# Heater.net
KiCad netlist of a schematic drawn in Altium Designer
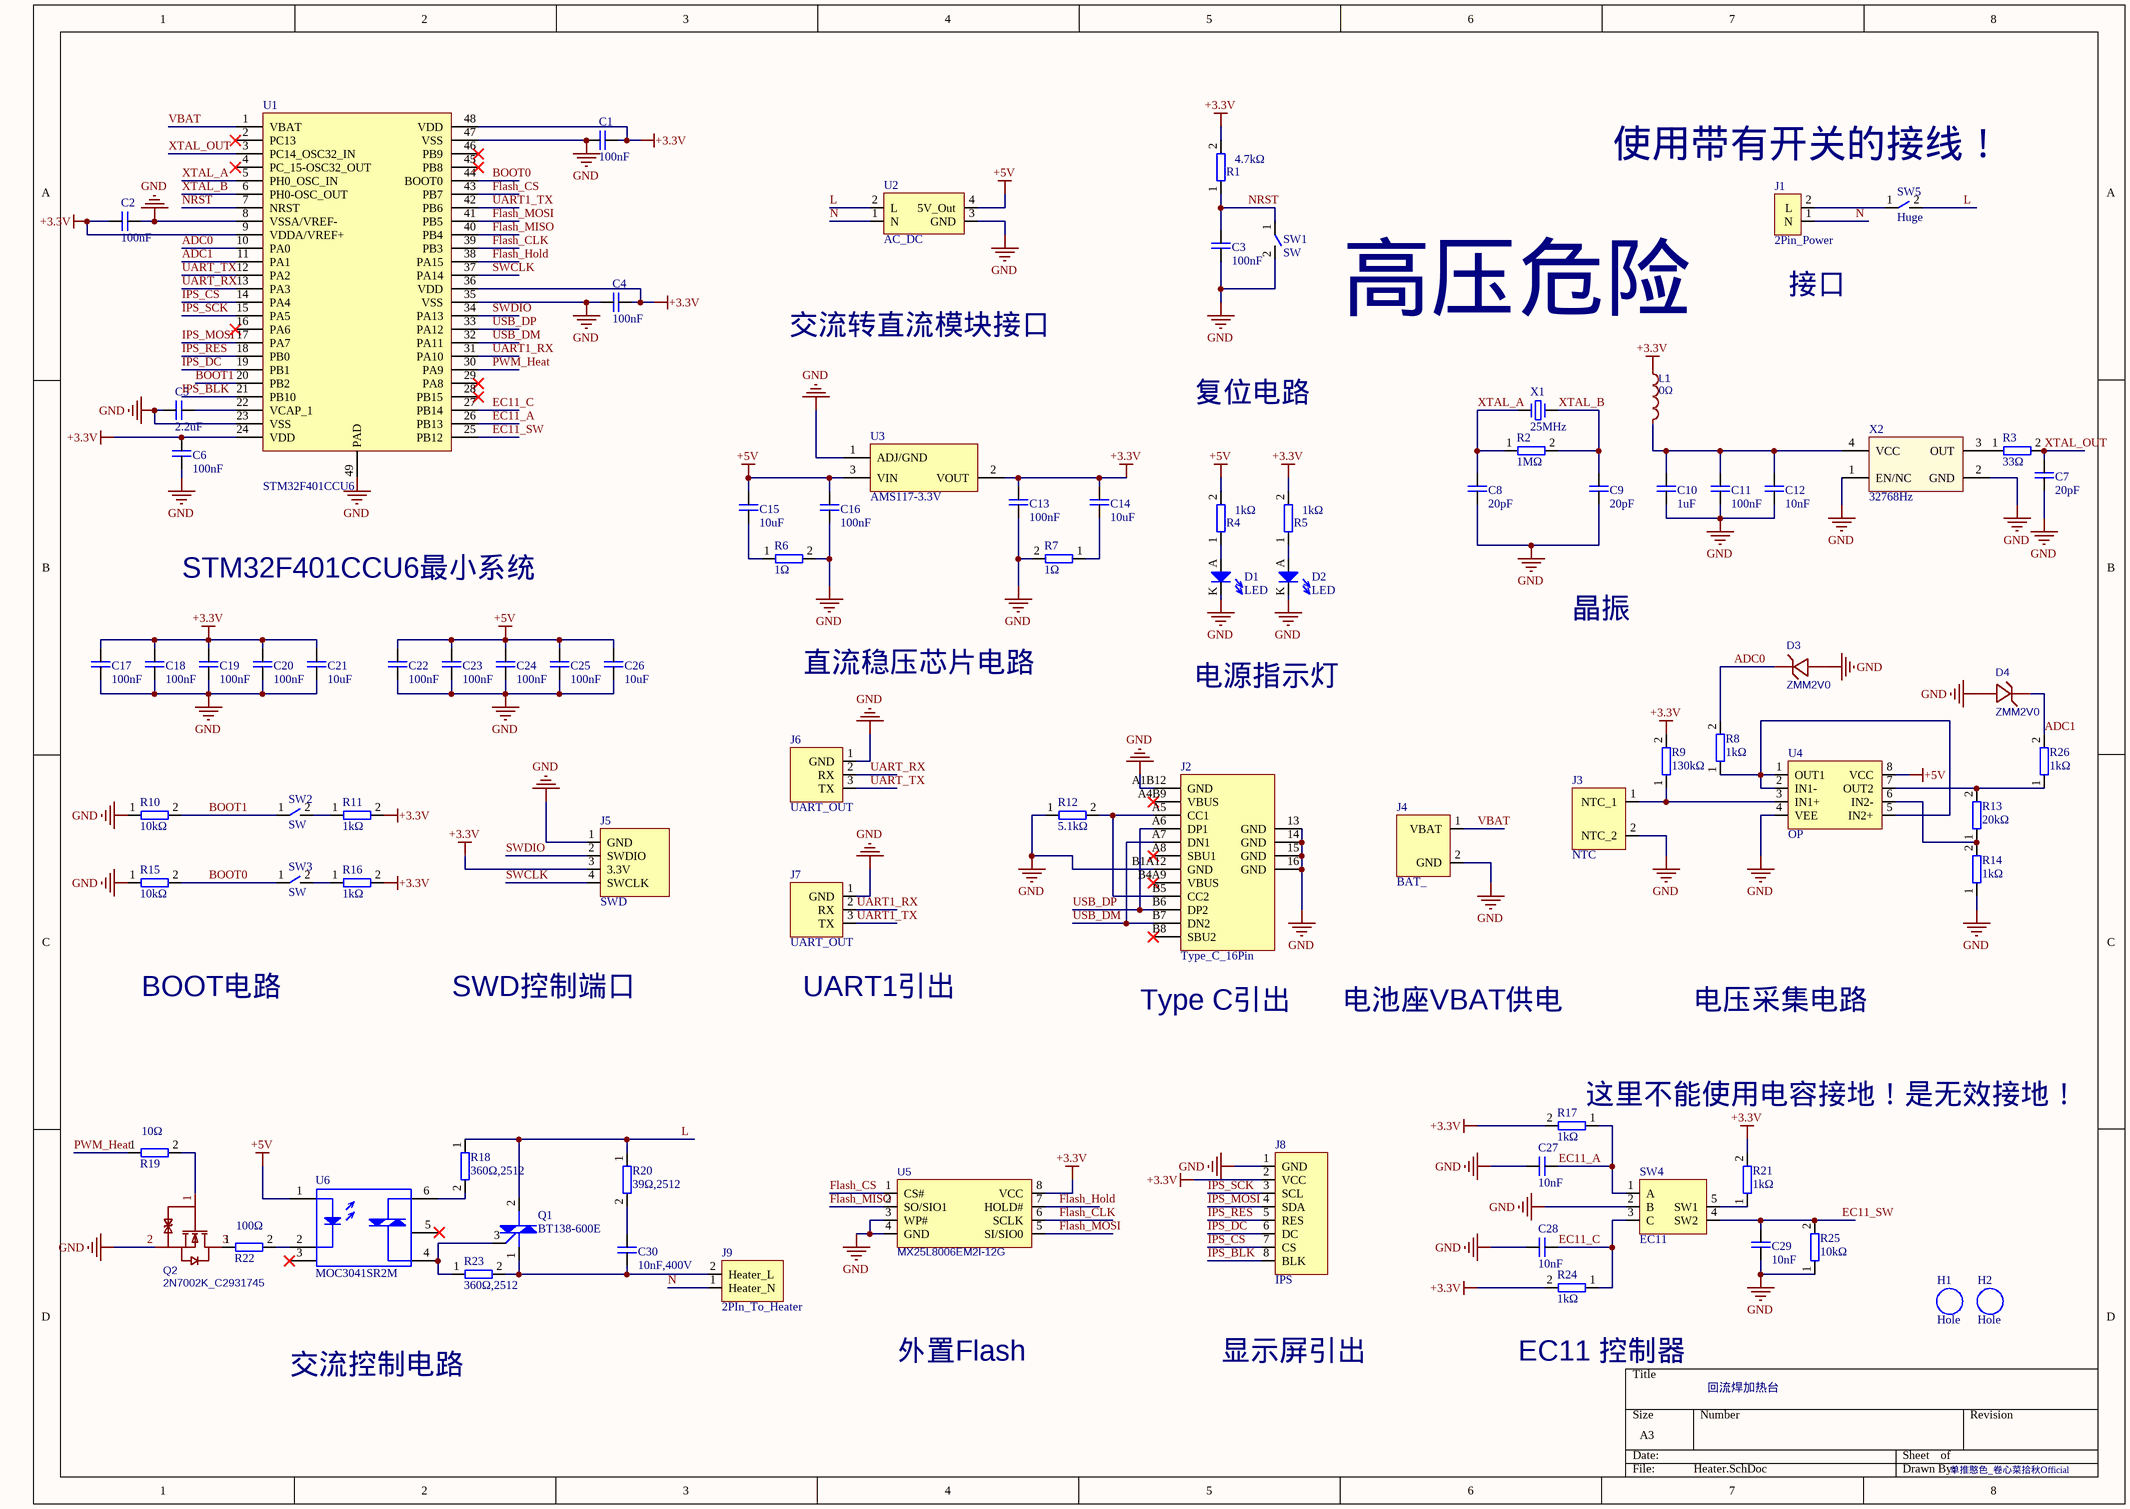
[diagram p0: Heater.SchDoc]

(export (version "E")
  (design (tool "Eeschema 10.0.6"))
  (components
    (comp (ref "C1") (value "100nF") (footprint "0603_C") (libsource (lib "Heater") (part "Capacitor")))
    (comp (ref "C2") (value "100nF") (footprint "0603_C") (libsource (lib "Heater") (part "Capacitor")))
    (comp (ref "C3") (value "100nF") (footprint "0603_C") (libsource (lib "Heater") (part "Capacitor")))
    (comp (ref "C4") (value "100nF") (footprint "0603_C") (libsource (lib "Heater") (part "Capacitor")))
    (comp (ref "C5") (value "2.2uF") (footprint "0603_C") (libsource (lib "Heater") (part "Capacitor")))
    (comp (ref "C6") (value "100nF") (footprint "0603_C") (libsource (lib "Heater") (part "Capacitor")))
    (comp (ref "C7") (value "20pF") (footprint "0603_C") (libsource (lib "Heater") (part "Capacitor")))
    (comp (ref "C8") (value "20pF") (footprint "0603_C") (libsource (lib "Heater") (part "Capacitor")))
    (comp (ref "C9") (value "20pF") (footprint "0603_C") (libsource (lib "Heater") (part "Capacitor")))
    (comp (ref "C10") (value "1uF") (footprint "0603_C") (libsource (lib "Heater") (part "Capacitor")))
    (comp (ref "C11") (value "100nF") (footprint "0603_C") (libsource (lib "Heater") (part "Capacitor")))
    (comp (ref "C12") (value "10nF") (footprint "0603_C") (libsource (lib "Heater") (part "Capacitor")))
    (comp (ref "C13") (value "100nF") (footprint "0603_C") (libsource (lib "Heater") (part "Capacitor")))
    (comp (ref "C14") (value "10uF") (footprint "0603_C") (libsource (lib "Heater") (part "Capacitor")))
    (comp (ref "C15") (value "10uF") (footprint "0603_C") (libsource (lib "Heater") (part "Capacitor")))
    (comp (ref "C16") (value "100nF") (footprint "0603_C") (libsource (lib "Heater") (part "Capacitor")))
    (comp (ref "C17") (value "100nF") (footprint "0603_C") (libsource (lib "Heater") (part "Capacitor")))
    (comp (ref "C18") (value "100nF") (footprint "0603_C") (libsource (lib "Heater") (part "Capacitor")))
    (comp (ref "C19") (value "100nF") (footprint "0603_C") (libsource (lib "Heater") (part "Capacitor")))
    (comp (ref "C20") (value "100nF") (footprint "0603_C") (libsource (lib "Heater") (part "Capacitor")))
    (comp (ref "C21") (value "10uF") (footprint "0603_C") (libsource (lib "Heater") (part "Capacitor")))
    (comp (ref "C22") (value "100nF") (footprint "0603_C") (libsource (lib "Heater") (part "Capacitor")))
    (comp (ref "C23") (value "100nF") (footprint "0603_C") (libsource (lib "Heater") (part "Capacitor")))
    (comp (ref "C24") (value "100nF") (footprint "0603_C") (libsource (lib "Heater") (part "Capacitor")))
    (comp (ref "C25") (value "100nF") (footprint "0603_C") (libsource (lib "Heater") (part "Capacitor")))
    (comp (ref "C26") (value "10uF") (footprint "0603_C") (libsource (lib "Heater") (part "Capacitor")))
    (comp (ref "C27") (value "10nF") (footprint "0603_C") (libsource (lib "Heater") (part "Capacitor")))
    (comp (ref "C28") (value "10nF") (footprint "0603_C") (libsource (lib "Heater") (part "Capacitor")))
    (comp (ref "C29") (value "10nF") (footprint "0603_C") (libsource (lib "Heater") (part "Capacitor")))
    (comp (ref "C30")
      (value "10nF,400V")
      (footprint "2PIN - BigCap")
      (libsource (lib "Heater") (part "Capacitor"))
    )
    (comp (ref "D1") (value "LED") (footprint "0603_LED") (libsource (lib "Heater") (part "LED")))
    (comp (ref "D2") (value "LED") (footprint "0603_LED") (libsource (lib "Heater") (part "LED")))
    (comp (ref "D3")
      (value "ZMM2V0")
      (footprint "LL-34_L3.5-W1.5-RD")
      (fields (field (name "BOM_SUPPLIER PART") "C8079"))
      (libsource (lib "Heater") (part "ZMM2V0"))
    )
    (comp (ref "D4")
      (value "ZMM2V0")
      (footprint "LL-34_L3.5-W1.5-RD")
      (fields (field (name "BOM_SUPPLIER PART") "C8079"))
      (libsource (lib "Heater") (part "ZMM2V0"))
    )
    (comp (ref "H1") (value "Hole") (footprint "Hole") (libsource (lib "Heater") (part "Hole")))
    (comp (ref "H2") (value "Hole") (footprint "Hole") (libsource (lib "Heater") (part "Hole")))
    (comp (ref "J1")
      (value "2Pin_Power")
      (footprint "Power-AC-2Pin")
      (libsource (lib "Heater") (part "2Pin_Power"))
    )
    (comp (ref "J2")
      (value "Type_C_16Pin")
      (footprint "USB-C-SMD_TYPEC-304-BCP16")
      (libsource (lib "Heater") (part "Type_C_16Pin"))
    )
    (comp (ref "J3") (value "NTC") (footprint "2PIN") (libsource (lib "Heater") (part "NTC")))
    (comp (ref "J4") (value "BAT_") (footprint "VBAT") (libsource (lib "Heater") (part "BAT_")))
    (comp (ref "J5") (value "SWD") (footprint "4PIN") (libsource (lib "Heater") (part "SWD")))
    (comp (ref "J6") (value "UART_OUT") (footprint "3Pin") (libsource (lib "Heater") (part "UART_OUT")))
    (comp (ref "J7") (value "UART_OUT") (footprint "3Pin") (libsource (lib "Heater") (part "UART_OUT")))
    (comp (ref "J8")
      (value "IPS")
      (footprint "IPS_8PIN - Simplified")
      (libsource (lib "Heater") (part "IPS"))
    )
    (comp (ref "J9")
      (value "2PIn_To_Heater")
      (footprint "CONN-TH_2.54-2P")
      (libsource (lib "Heater") (part "2PIn_To_Heater"))
    )
    (comp (ref "L1")
      (value "0Ω")
      (footprint "L0603")
      (fields
        (field (name "BOM_MANUFACTURER PART") "CBW160808U000T")
        (field (name "BOM_SUPPLIER PART") "C139173")
      )
      (libsource (lib "Heater") (part "0Ω"))
    )
    (comp (ref "Q1")
      (value "BT138-600E")
      (footprint "TO-220-3_L10.0-W4.5-P2.54-L")
      (libsource (lib "Heater") (part "BT138-600E"))
    )
    (comp (ref "Q2")
      (value "2N7002K_C2931745")
      (footprint "SOT-23-3_NMOS")
      (fields
        (field (name "BOM_SUPPLIER PART") "C2931745")
        (field (name "BOM_MANUFACTURER PART") "2N7002K")
        (field (name "CONTRIBUTOR") "LCSC")
      )
      (libsource (lib "Heater") (part "2N7002K_C2931745"))
    )
    (comp (ref "R1") (value "4.7kΩ") (footprint "0603 _R") (libsource (lib "Heater") (part "Resistor")))
    (comp (ref "R2") (value "1MΩ") (footprint "0603 _R") (libsource (lib "Heater") (part "Resistor")))
    (comp (ref "R3") (value "33Ω") (footprint "0603 _R") (libsource (lib "Heater") (part "Resistor")))
    (comp (ref "R4") (value "1kΩ") (footprint "0603 _R") (libsource (lib "Heater") (part "Resistor")))
    (comp (ref "R5") (value "1kΩ") (footprint "0603 _R") (libsource (lib "Heater") (part "Resistor")))
    (comp (ref "R6") (value "1Ω") (footprint "0603 _R") (libsource (lib "Heater") (part "Resistor")))
    (comp (ref "R7") (value "1Ω") (footprint "0603 _R") (libsource (lib "Heater") (part "Resistor")))
    (comp (ref "R8") (value "1kΩ") (footprint "0603 _R") (libsource (lib "Heater") (part "Resistor")))
    (comp (ref "R9") (value "130kΩ") (footprint "0603 _R") (libsource (lib "Heater") (part "Resistor")))
    (comp (ref "R10") (value "10kΩ") (footprint "0603 _R") (libsource (lib "Heater") (part "Resistor")))
    (comp (ref "R11") (value "1kΩ") (footprint "0603 _R") (libsource (lib "Heater") (part "Resistor")))
    (comp (ref "R12") (value "5.1kΩ") (footprint "0603 _R") (libsource (lib "Heater") (part "Resistor")))
    (comp (ref "R13") (value "20kΩ") (footprint "0603 _R") (libsource (lib "Heater") (part "Resistor")))
    (comp (ref "R14") (value "1kΩ") (footprint "0603 _R") (libsource (lib "Heater") (part "Resistor")))
    (comp (ref "R15") (value "10kΩ") (footprint "0603 _R") (libsource (lib "Heater") (part "Resistor")))
    (comp (ref "R16") (value "1kΩ") (footprint "0603 _R") (libsource (lib "Heater") (part "Resistor")))
    (comp (ref "R17") (value "1kΩ") (footprint "0603 _R") (libsource (lib "Heater") (part "Resistor")))
    (comp (ref "R18") (value "360Ω,2512") (footprint "2512_R") (libsource (lib "Heater") (part "Resistor")))
    (comp (ref "R19") (value "10Ω") (footprint "0603 _R") (libsource (lib "Heater") (part "Resistor")))
    (comp (ref "R20") (value "39Ω,2512") (footprint "2512_R") (libsource (lib "Heater") (part "Resistor")))
    (comp (ref "R21") (value "1kΩ") (footprint "0603 _R") (libsource (lib "Heater") (part "Resistor")))
    (comp (ref "R22") (value "100Ω") (footprint "0603 _R") (libsource (lib "Heater") (part "Resistor")))
    (comp (ref "R23") (value "360Ω,2512") (footprint "2512_R") (libsource (lib "Heater") (part "Resistor")))
    (comp (ref "R24") (value "1kΩ") (footprint "0603 _R") (libsource (lib "Heater") (part "Resistor")))
    (comp (ref "R25") (value "10kΩ") (footprint "0603 _R") (libsource (lib "Heater") (part "Resistor")))
    (comp (ref "R26") (value "1kΩ") (footprint "0603 _R") (libsource (lib "Heater") (part "Resistor")))
    (comp (ref "SW1")
      (value "SW")
      (footprint "SW-SMD_5P-L6.4-W6.2-P4.50-LS8.2-TL")
      (libsource (lib "Heater") (part "SW"))
    )
    (comp (ref "SW2")
      (value "SW")
      (footprint "SW-SMD_5P-L6.4-W6.2-P4.50-LS8.2-TL")
      (libsource (lib "Heater") (part "SW"))
    )
    (comp (ref "SW3")
      (value "SW")
      (footprint "SW-SMD_5P-L6.4-W6.2-P4.50-LS8.2-TL")
      (libsource (lib "Heater") (part "SW"))
    )
    (comp (ref "SW4") (value "EC11") (footprint "EC11") (libsource (lib "Heater") (part "EC11")))
    (comp (ref "SW5") (value "Huge") (footprint "SW") (libsource (lib "Heater") (part "SW_DA")))
    (comp (ref "U1")
      (value "STM32F401CCU6")
      (footprint "UFQFPN-48_L7.0-W7.0-P0.50-BL-EP")
      (libsource (lib "Heater") (part "STM32F401CCU6"))
    )
    (comp (ref "U2") (value "AC_DC") (footprint "AC_TO_DC") (libsource (lib "Heater") (part "AC_DC")))
    (comp (ref "U3")
      (value "AMS117-3.3V")
      (footprint "SOT-223-3_L6.5-W3.4-P2.30-LS7.0-BR")
      (libsource (lib "Heater") (part "ASM1117-3.3V"))
    )
    (comp (ref "U4") (value "OP") (footprint "SOP-8_OP") (libsource (lib "Heater") (part "OP")))
    (comp (ref "U5")
      (value "MX25L8006EM2I-12G")
      (footprint "SOP-8_L5.3-W5.3-P1.27-LS8.0-BL")
      (fields (field (name "BOM_SUPPLIER PART") "C71947"))
      (libsource (lib "Heater") (part "MX25L8006EM2I-12G"))
    )
    (comp (ref "U6")
      (value "MOC3041SR2M")
      (footprint "DIP-6_MO")
      (libsource (lib "Heater") (part "MOC3041SR2M"))
    )
    (comp (ref "X1")
      (value "25MHz")
      (footprint "HC-49US_L11.0-W4.6-P4.88 - duplicate")
      (description "2脚无源脚晶振")
      (fields (field (name "版权归属") "源创客"))
      (libsource (lib "Heater") (part "XTAL-2P"))
    )
    (comp (ref "X2")
      (value "32768Hz")
      (footprint "OSC 3225")
      (description "4脚有源晶振")
      (fields (field (name "版权归属") "源创客"))
      (libsource (lib "Heater") (part "XTAL-ACT-4P"))
    )
  )
  (nets
    (net (code "1") (name "+3.3V") (class "Default")
      (node (ref "C1") (pin "1") (pintype "passive"))
      (node (ref "C13") (pin "1") (pintype "passive"))
      (node (ref "C14") (pin "1") (pintype "passive"))
      (node (ref "C17") (pin "1") (pintype "passive"))
      (node (ref "C18") (pin "1") (pintype "passive"))
      (node (ref "C19") (pin "1") (pintype "passive"))
      (node (ref "C2") (pin "1") (pintype "passive"))
      (node (ref "C20") (pin "1") (pintype "passive"))
      (node (ref "C21") (pin "1") (pintype "passive"))
      (node (ref "C4") (pin "1") (pintype "passive"))
      (node (ref "C6") (pin "2") (pintype "passive"))
      (node (ref "J5") (pin "3") (pinfunction "3.3V_3") (pintype "passive"))
      (node (ref "J8") (pin "2") (pinfunction "VCC_2") (pintype "passive"))
      (node (ref "L1") (pin "1") (pinfunction "1_1") (pintype "passive"))
      (node (ref "R1") (pin "2") (pintype "passive"))
      (node (ref "R11") (pin "2") (pintype "passive"))
      (node (ref "R16") (pin "2") (pintype "passive"))
      (node (ref "R17") (pin "2") (pintype "passive"))
      (node (ref "R21") (pin "2") (pintype "passive"))
      (node (ref "R24") (pin "2") (pintype "passive"))
      (node (ref "R5") (pin "2") (pintype "passive"))
      (node (ref "R9") (pin "2") (pintype "passive"))
      (node (ref "U1") (pin "24") (pinfunction "VDD_24") (pintype "passive"))
      (node (ref "U1") (pin "36") (pinfunction "VDD_36") (pintype "passive"))
      (node (ref "U1") (pin "48") (pinfunction "VDD_48") (pintype "passive"))
      (node (ref "U1") (pin "9") (pinfunction "VDDA/VREF+_9") (pintype "passive"))
      (node (ref "U3") (pin "2") (pinfunction "VOUT_2") (pintype "passive"))
      (node (ref "U5") (pin "8") (pinfunction "VCC_8") (pintype "passive"))
    )
    (net (code "2") (name "+5V") (class "Default")
      (node (ref "C15") (pin "2") (pintype "passive"))
      (node (ref "C16") (pin "2") (pintype "passive"))
      (node (ref "C22") (pin "1") (pintype "passive"))
      (node (ref "C23") (pin "1") (pintype "passive"))
      (node (ref "C24") (pin "1") (pintype "passive"))
      (node (ref "C25") (pin "1") (pintype "passive"))
      (node (ref "C26") (pin "1") (pintype "passive"))
      (node (ref "R4") (pin "2") (pintype "passive"))
      (node (ref "U2") (pin "4") (pinfunction "5V_Out_4") (pintype "passive"))
      (node (ref "U3") (pin "3") (pinfunction "VIN_3") (pintype "passive"))
      (node (ref "U4") (pin "8") (pinfunction "VCC_8") (pintype "passive"))
      (node (ref "U6") (pin "1") (pinfunction "Anode_1") (pintype "passive"))
    )
    (net (code "3") (name "/ADC0") (class "Default")
      (node (ref "D3") (pin "1") (pinfunction "C_1") (pintype "passive"))
      (node (ref "R8") (pin "2") (pintype "passive"))
      (node (ref "U1") (pin "10") (pinfunction "PA0_10") (pintype "passive"))
    )
    (net (code "4") (name "/ADC1") (class "Default")
      (node (ref "D4") (pin "1") (pinfunction "C_1") (pintype "passive"))
      (node (ref "R26") (pin "2") (pintype "passive"))
      (node (ref "U1") (pin "11") (pinfunction "PA1_11") (pintype "passive"))
    )
    (net (code "5") (name "/BOOT0") (class "Default")
      (node (ref "R15") (pin "2") (pintype "passive"))
      (node (ref "SW3") (pin "1") (pinfunction "1_1") (pintype "passive"))
      (node (ref "U1") (pin "44") (pinfunction "BOOT0_44") (pintype "passive"))
    )
    (net (code "6") (name "/BOOT1") (class "Default")
      (node (ref "R10") (pin "2") (pintype "passive"))
      (node (ref "SW2") (pin "1") (pinfunction "1_1") (pintype "passive"))
      (node (ref "U1") (pin "20") (pinfunction "PB2_20") (pintype "passive"))
    )
    (net (code "7") (name "/EC11_A") (class "Default")
      (node (ref "C27") (pin "2") (pintype "passive"))
      (node (ref "R17") (pin "1") (pintype "passive"))
      (node (ref "SW4") (pin "1") (pinfunction "A_1") (pintype "passive"))
      (node (ref "U1") (pin "26") (pinfunction "PB13_26") (pintype "passive"))
    )
    (net (code "8") (name "/EC11_C") (class "Default")
      (node (ref "C28") (pin "2") (pintype "passive"))
      (node (ref "R24") (pin "1") (pintype "passive"))
      (node (ref "SW4") (pin "3") (pinfunction "C_3") (pintype "passive"))
      (node (ref "U1") (pin "27") (pinfunction "PB14_27") (pintype "passive"))
    )
    (net (code "9") (name "/EC11_SW") (class "Default")
      (node (ref "C29") (pin "1") (pintype "passive"))
      (node (ref "R25") (pin "2") (pintype "passive"))
      (node (ref "SW4") (pin "4") (pinfunction "SW2_4") (pintype "passive"))
      (node (ref "U1") (pin "25") (pinfunction "PB12_25") (pintype "passive"))
    )
    (net (code "10") (name "/Flash_CLK") (class "Default")
      (node (ref "U1") (pin "39") (pinfunction "PB3_39") (pintype "passive"))
      (node (ref "U5") (pin "6") (pinfunction "SCLK_6") (pintype "passive"))
    )
    (net (code "11") (name "/Flash_CS") (class "Default")
      (node (ref "U1") (pin "43") (pinfunction "PB7_43") (pintype "passive"))
      (node (ref "U5") (pin "1") (pinfunction "CS#_1") (pintype "passive"))
    )
    (net (code "12") (name "/Flash_Hold") (class "Default")
      (node (ref "U1") (pin "38") (pinfunction "PA15_38") (pintype "passive"))
      (node (ref "U5") (pin "7") (pinfunction "HOLD#_7") (pintype "passive"))
    )
    (net (code "13") (name "/Flash_MISO") (class "Default")
      (node (ref "U1") (pin "40") (pinfunction "PB4_40") (pintype "passive"))
      (node (ref "U5") (pin "2") (pinfunction "SO/SIO1_2") (pintype "passive"))
    )
    (net (code "14") (name "/Flash_MOSI") (class "Default")
      (node (ref "U1") (pin "41") (pinfunction "PB5_41") (pintype "passive"))
      (node (ref "U5") (pin "5") (pinfunction "SI/SIO0_5") (pintype "passive"))
    )
    (net (code "15") (name "/IPS_BLK") (class "Default")
      (node (ref "J8") (pin "8") (pinfunction "BLK_8") (pintype "passive"))
      (node (ref "U1") (pin "21") (pinfunction "PB10_21") (pintype "passive"))
    )
    (net (code "16") (name "/IPS_CS") (class "Default")
      (node (ref "J8") (pin "7") (pinfunction "CS_7") (pintype "passive"))
      (node (ref "U1") (pin "14") (pinfunction "PA4_14") (pintype "passive"))
    )
    (net (code "17") (name "/IPS_DC") (class "Default")
      (node (ref "J8") (pin "6") (pinfunction "DC_6") (pintype "passive"))
      (node (ref "U1") (pin "19") (pinfunction "PB1_19") (pintype "passive"))
    )
    (net (code "18") (name "/IPS_MOSI") (class "Default")
      (node (ref "J8") (pin "4") (pinfunction "SDA_4") (pintype "passive"))
      (node (ref "U1") (pin "17") (pinfunction "PA7_17") (pintype "passive"))
    )
    (net (code "19") (name "/IPS_RES") (class "Default")
      (node (ref "J8") (pin "5") (pinfunction "RES_5") (pintype "passive"))
      (node (ref "U1") (pin "18") (pinfunction "PB0_18") (pintype "passive"))
    )
    (net (code "20") (name "/IPS_SCK") (class "Default")
      (node (ref "J8") (pin "3") (pinfunction "SCL_3") (pintype "passive"))
      (node (ref "U1") (pin "15") (pinfunction "PA5_15") (pintype "passive"))
    )
    (net (code "21") (name "/L") (class "Default")
      (node (ref "Q1") (pin "2") (pinfunction "2_2") (pintype "passive"))
      (node (ref "R18") (pin "1") (pintype "passive"))
      (node (ref "R20") (pin "1") (pintype "passive"))
      (node (ref "SW5") (pin "2") (pinfunction "2_2") (pintype "passive"))
      (node (ref "U2") (pin "2") (pinfunction "L_2") (pintype "passive"))
    )
    (net (code "22") (name "/N") (class "Default")
      (node (ref "J1") (pin "1") (pinfunction "N_1") (pintype "passive"))
      (node (ref "J9") (pin "1") (pinfunction "Heater_N_1") (pintype "passive"))
      (node (ref "U2") (pin "1") (pinfunction "N_1") (pintype "passive"))
    )
    (net (code "23") (name "/NRST") (class "Default")
      (node (ref "C3") (pin "1") (pintype "passive"))
      (node (ref "R1") (pin "1") (pintype "passive"))
      (node (ref "SW1") (pin "1") (pinfunction "1_1") (pintype "passive"))
      (node (ref "U1") (pin "7") (pinfunction "NRST_7") (pintype "passive"))
    )
    (net (code "24") (name "/PWM_Heat") (class "Default")
      (node (ref "R19") (pin "1") (pintype "passive"))
      (node (ref "U1") (pin "30") (pinfunction "PA9_30") (pintype "passive"))
    )
    (net (code "25") (name "/SWCLK") (class "Default")
      (node (ref "J5") (pin "4") (pinfunction "SWCLK_4") (pintype "passive"))
      (node (ref "U1") (pin "37") (pinfunction "PA14_37") (pintype "passive"))
    )
    (net (code "26") (name "/SWDIO") (class "Default")
      (node (ref "J5") (pin "2") (pinfunction "SWDIO_2") (pintype "passive"))
      (node (ref "U1") (pin "34") (pinfunction "PA13_34") (pintype "passive"))
    )
    (net (code "27") (name "/UART1_RX") (class "Default")
      (node (ref "J7") (pin "2") (pinfunction "RX_2") (pintype "passive"))
      (node (ref "U1") (pin "31") (pinfunction "PA10_31") (pintype "passive"))
    )
    (net (code "28") (name "/UART1_TX") (class "Default")
      (node (ref "J7") (pin "3") (pinfunction "TX_3") (pintype "passive"))
      (node (ref "U1") (pin "42") (pinfunction "PB6_42") (pintype "passive"))
    )
    (net (code "29") (name "/UART_RX") (class "Default")
      (node (ref "J6") (pin "2") (pinfunction "RX_2") (pintype "passive"))
      (node (ref "U1") (pin "13") (pinfunction "PA3_13") (pintype "passive"))
    )
    (net (code "30") (name "/UART_TX") (class "Default")
      (node (ref "J6") (pin "3") (pinfunction "TX_3") (pintype "passive"))
      (node (ref "U1") (pin "12") (pinfunction "PA2_12") (pintype "passive"))
    )
    (net (code "31") (name "/USB_DM") (class "Default")
      (node (ref "J2") (pin "A7") (pinfunction "DN1_A7") (pintype "passive"))
      (node (ref "J2") (pin "B7") (pinfunction "DN2_B7") (pintype "passive"))
      (node (ref "U1") (pin "32") (pinfunction "PA11_32") (pintype "passive"))
    )
    (net (code "32") (name "/USB_DP") (class "Default")
      (node (ref "J2") (pin "A6") (pinfunction "DP1_A6") (pintype "passive"))
      (node (ref "J2") (pin "B6") (pinfunction "DP2_B6") (pintype "passive"))
      (node (ref "U1") (pin "33") (pinfunction "PA12_33") (pintype "passive"))
    )
    (net (code "33") (name "/VBAT") (class "Default")
      (node (ref "J4") (pin "1") (pinfunction "VBAT_1") (pintype "passive"))
      (node (ref "U1") (pin "1") (pinfunction "VBAT_1") (pintype "passive"))
    )
    (net (code "34") (name "/XTAL_A") (class "Default")
      (node (ref "C8") (pin "1") (pintype "passive"))
      (node (ref "R2") (pin "1") (pintype "passive"))
      (node (ref "U1") (pin "5") (pinfunction "PH0_OSC_IN_5") (pintype "passive"))
      (node (ref "X1") (pin "1") (pinfunction "1_1") (pintype "passive"))
    )
    (net (code "35") (name "/XTAL_B") (class "Default")
      (node (ref "C9") (pin "1") (pintype "passive"))
      (node (ref "R2") (pin "2") (pintype "passive"))
      (node (ref "U1") (pin "6") (pinfunction "PH0-OSC_OUT_6") (pintype "passive"))
      (node (ref "X1") (pin "2") (pinfunction "2_2") (pintype "passive"))
    )
    (net (code "36") (name "/XTAL_OUT") (class "Default")
      (node (ref "C7") (pin "1") (pintype "passive"))
      (node (ref "R3") (pin "2") (pintype "passive"))
      (node (ref "U1") (pin "3") (pinfunction "PC14_OSC32_IN_3") (pintype "passive"))
    )
    (net (code "37") (name "GND") (class "Default")
      (node (ref "C1") (pin "2") (pintype "passive"))
      (node (ref "C10") (pin "2") (pintype "passive"))
      (node (ref "C11") (pin "2") (pintype "passive"))
      (node (ref "C12") (pin "2") (pintype "passive"))
      (node (ref "C13") (pin "2") (pintype "passive"))
      (node (ref "C16") (pin "1") (pintype "passive"))
      (node (ref "C17") (pin "2") (pintype "passive"))
      (node (ref "C18") (pin "2") (pintype "passive"))
      (node (ref "C19") (pin "2") (pintype "passive"))
      (node (ref "C2") (pin "2") (pintype "passive"))
      (node (ref "C20") (pin "2") (pintype "passive"))
      (node (ref "C21") (pin "2") (pintype "passive"))
      (node (ref "C22") (pin "2") (pintype "passive"))
      (node (ref "C23") (pin "2") (pintype "passive"))
      (node (ref "C24") (pin "2") (pintype "passive"))
      (node (ref "C25") (pin "2") (pintype "passive"))
      (node (ref "C26") (pin "2") (pintype "passive"))
      (node (ref "C27") (pin "1") (pintype "passive"))
      (node (ref "C28") (pin "1") (pintype "passive"))
      (node (ref "C29") (pin "2") (pintype "passive"))
      (node (ref "C3") (pin "2") (pintype "passive"))
      (node (ref "C4") (pin "2") (pintype "passive"))
      (node (ref "C5") (pin "1") (pintype "passive"))
      (node (ref "C6") (pin "1") (pintype "passive"))
      (node (ref "C7") (pin "2") (pintype "passive"))
      (node (ref "C8") (pin "2") (pintype "passive"))
      (node (ref "C9") (pin "2") (pintype "passive"))
      (node (ref "D1") (pin "K") (pintype "passive"))
      (node (ref "D2") (pin "K") (pintype "passive"))
      (node (ref "D3") (pin "2") (pinfunction "A_2") (pintype "passive"))
      (node (ref "D4") (pin "2") (pinfunction "A_2") (pintype "passive"))
      (node (ref "J2") (pin "13") (pinfunction "GND_13") (pintype "passive"))
      (node (ref "J2") (pin "14") (pinfunction "GND_14") (pintype "passive"))
      (node (ref "J2") (pin "15") (pinfunction "GND_15") (pintype "passive"))
      (node (ref "J2") (pin "16") (pinfunction "GND_16") (pintype "passive"))
      (node (ref "J2") (pin "A1B12") (pinfunction "GND_A1B12") (pintype "passive"))
      (node (ref "J2") (pin "B1A12") (pinfunction "GND_B1A12") (pintype "passive"))
      (node (ref "J3") (pin "2") (pinfunction "NTC_2_2") (pintype "passive"))
      (node (ref "J4") (pin "2") (pinfunction "GND_2") (pintype "passive"))
      (node (ref "J5") (pin "1") (pinfunction "GND_1") (pintype "passive"))
      (node (ref "J6") (pin "1") (pinfunction "GND_1") (pintype "passive"))
      (node (ref "J7") (pin "1") (pinfunction "GND_1") (pintype "passive"))
      (node (ref "J8") (pin "1") (pinfunction "GND_1") (pintype "passive"))
      (node (ref "Q2") (pin "2") (pinfunction "S_2") (pintype "passive"))
      (node (ref "R10") (pin "1") (pintype "passive"))
      (node (ref "R12") (pin "1") (pintype "passive"))
      (node (ref "R14") (pin "1") (pintype "passive"))
      (node (ref "R15") (pin "1") (pintype "passive"))
      (node (ref "R25") (pin "1") (pintype "passive"))
      (node (ref "R6") (pin "2") (pintype "passive"))
      (node (ref "R7") (pin "2") (pintype "passive"))
      (node (ref "SW1") (pin "2") (pinfunction "2_2") (pintype "passive"))
      (node (ref "SW4") (pin "2") (pinfunction "B_2") (pintype "passive"))
      (node (ref "U1") (pin "23") (pinfunction "VSS_23") (pintype "passive"))
      (node (ref "U1") (pin "35") (pinfunction "VSS_35") (pintype "passive"))
      (node (ref "U1") (pin "47") (pinfunction "VSS_47") (pintype "passive"))
      (node (ref "U1") (pin "49") (pinfunction "PAD_49") (pintype "passive"))
      (node (ref "U1") (pin "8") (pinfunction "VSSA/VREF-_8") (pintype "passive"))
      (node (ref "U2") (pin "3") (pinfunction "GND_3") (pintype "passive"))
      (node (ref "U3") (pin "1") (pinfunction "ADJ/GND_1") (pintype "passive"))
      (node (ref "U4") (pin "4") (pinfunction "VEE_4") (pintype "passive"))
      (node (ref "U5") (pin "3") (pinfunction "WP#_3") (pintype "passive"))
      (node (ref "U5") (pin "4") (pinfunction "GND_4") (pintype "passive"))
      (node (ref "X2") (pin "1") (pinfunction "EN/NC_1") (pintype "passive"))
      (node (ref "X2") (pin "2") (pinfunction "GND_2") (pintype "passive"))
    )
    (net (code "38") (name "Net-(C14-Pad2)") (class "Default")
      (node (ref "C14") (pin "2") (pintype "passive"))
      (node (ref "R7") (pin "1") (pintype "passive"))
    )
    (net (code "39") (name "Net-(C15-Pad1)") (class "Default")
      (node (ref "C15") (pin "1") (pintype "passive"))
      (node (ref "R6") (pin "1") (pintype "passive"))
    )
    (net (code "40") (name "Net-(C30-Pad2)") (class "Default")
      (node (ref "C30") (pin "2") (pintype "passive"))
      (node (ref "R20") (pin "2") (pintype "passive"))
    )
    (net (code "41") (name "Net-(D1-PadA)") (class "Default")
      (node (ref "D1") (pin "A") (pintype "passive"))
      (node (ref "R4") (pin "1") (pintype "passive"))
    )
    (net (code "42") (name "Net-(D2-PadA)") (class "Default")
      (node (ref "D2") (pin "A") (pintype "passive"))
      (node (ref "R5") (pin "1") (pintype "passive"))
    )
    (net (code "43") (name "Net-(J1-L)") (class "Default")
      (node (ref "J1") (pin "2") (pinfunction "L_2") (pintype "passive"))
      (node (ref "SW5") (pin "1") (pinfunction "1_1") (pintype "passive"))
    )
    (net (code "44") (name "Net-(J2-CC1)") (class "Default")
      (node (ref "J2") (pin "A5") (pinfunction "CC1_A5") (pintype "passive"))
      (node (ref "J2") (pin "B5") (pinfunction "CC2_B5") (pintype "passive"))
      (node (ref "R12") (pin "2") (pintype "passive"))
    )
    (net (code "45") (name "Net-(J3-NTC_1)") (class "Default")
      (node (ref "J3") (pin "1") (pinfunction "NTC_1_1") (pintype "passive"))
      (node (ref "R9") (pin "1") (pintype "passive"))
      (node (ref "U4") (pin "3") (pinfunction "IN1+_3") (pintype "passive"))
    )
    (net (code "46") (name "Net-(J9-Heater_L)") (class "Default")
      (node (ref "C30") (pin "1") (pintype "passive"))
      (node (ref "J9") (pin "2") (pinfunction "Heater_L_2") (pintype "passive"))
      (node (ref "Q1") (pin "1") (pinfunction "1_1") (pintype "passive"))
      (node (ref "R23") (pin "2") (pintype "passive"))
    )
    (net (code "47") (name "Net-(Q1-Pad3)") (class "Default")
      (node (ref "Q1") (pin "3") (pinfunction "3_3") (pintype "passive"))
      (node (ref "R23") (pin "1") (pintype "passive"))
      (node (ref "U6") (pin "4") (pinfunction "Main_Term_4") (pintype "passive"))
    )
    (net (code "48") (name "Net-(Q2-D)") (class "Default")
      (node (ref "Q2") (pin "3") (pinfunction "D_3") (pintype "passive"))
      (node (ref "R22") (pin "1") (pintype "passive"))
    )
    (net (code "49") (name "Net-(Q2-G)") (class "Default")
      (node (ref "Q2") (pin "1") (pinfunction "G_1") (pintype "passive"))
      (node (ref "R19") (pin "2") (pintype "passive"))
    )
    (net (code "50") (name "Net-(R11-Pad1)") (class "Default")
      (node (ref "R11") (pin "1") (pintype "passive"))
      (node (ref "SW2") (pin "2") (pinfunction "2_2") (pintype "passive"))
    )
    (net (code "51") (name "Net-(R16-Pad1)") (class "Default")
      (node (ref "R16") (pin "1") (pintype "passive"))
      (node (ref "SW3") (pin "2") (pinfunction "2_2") (pintype "passive"))
    )
    (net (code "52") (name "Net-(R18-Pad2)") (class "Default")
      (node (ref "R18") (pin "2") (pintype "passive"))
      (node (ref "U6") (pin "6") (pinfunction "Main_Term_6") (pintype "passive"))
    )
    (net (code "53") (name "Net-(SW4-SW1)") (class "Default")
      (node (ref "R21") (pin "1") (pintype "passive"))
      (node (ref "SW4") (pin "5") (pinfunction "SW1_5") (pintype "passive"))
    )
    (net (code "54") (name "Net-(U1-VCAP_1)") (class "Default")
      (node (ref "C5") (pin "2") (pintype "passive"))
      (node (ref "U1") (pin "22") (pinfunction "VCAP_1_22") (pintype "passive"))
    )
    (net (code "55") (name "Net-(U4-IN1-)") (class "Default")
      (node (ref "R8") (pin "1") (pintype "passive"))
      (node (ref "U4") (pin "1") (pinfunction "OUT1_1") (pintype "passive"))
      (node (ref "U4") (pin "2") (pinfunction "IN1-_2") (pintype "passive"))
      (node (ref "U4") (pin "5") (pinfunction "IN2+_5") (pintype "passive"))
    )
    (net (code "56") (name "Net-(U4-IN2-)") (class "Default")
      (node (ref "R13") (pin "1") (pintype "passive"))
      (node (ref "R14") (pin "2") (pintype "passive"))
      (node (ref "U4") (pin "6") (pinfunction "IN2-_6") (pintype "passive"))
    )
    (net (code "57") (name "Net-(U4-OUT2)") (class "Default")
      (node (ref "R13") (pin "2") (pintype "passive"))
      (node (ref "R26") (pin "1") (pintype "passive"))
      (node (ref "U4") (pin "7") (pinfunction "OUT2_7") (pintype "passive"))
    )
    (net (code "58") (name "Net-(U6-Cathode)") (class "Default")
      (node (ref "R22") (pin "2") (pintype "passive"))
      (node (ref "U6") (pin "2") (pinfunction "Cathode_2") (pintype "passive"))
    )
    (net (code "59") (name "Net-(X2-OUT)") (class "Default")
      (node (ref "R3") (pin "1") (pintype "passive"))
      (node (ref "X2") (pin "3") (pinfunction "OUT_3") (pintype "passive"))
    )
    (net (code "60") (name "Net-(X2-VCC)") (class "Default")
      (node (ref "C10") (pin "1") (pintype "passive"))
      (node (ref "C11") (pin "1") (pintype "passive"))
      (node (ref "C12") (pin "1") (pintype "passive"))
      (node (ref "L1") (pin "2") (pinfunction "2_2") (pintype "passive"))
      (node (ref "X2") (pin "4") (pinfunction "VCC_4") (pintype "passive"))
    )
    (net (code "61") (name "unconnected-(J2-SBU1-PadA8)") (class "Default")
      (node (ref "J2") (pin "A8") (pinfunction "SBU1_A8") (pintype "passive+no_connect"))
    )
    (net (code "62") (name "unconnected-(J2-SBU2-PadB8)") (class "Default")
      (node (ref "J2") (pin "B8") (pinfunction "SBU2_B8") (pintype "passive+no_connect"))
    )
    (net (code "63") (name "unconnected-(J2-VBUS-PadA4B9)") (class "Default")
      (node (ref "J2") (pin "A4B9") (pinfunction "VBUS_A4B9") (pintype "passive+no_connect"))
    )
    (net (code "64") (name "unconnected-(J2-VBUS-PadB4A9)") (class "Default")
      (node (ref "J2") (pin "B4A9") (pinfunction "VBUS_B4A9") (pintype "passive+no_connect"))
    )
    (net (code "65") (name "unconnected-(U1-PA6-Pad16)") (class "Default")
      (node (ref "U1") (pin "16") (pinfunction "PA6_16") (pintype "passive+no_connect"))
    )
    (net (code "66") (name "unconnected-(U1-PA8-Pad29)") (class "Default")
      (node (ref "U1") (pin "29") (pinfunction "PA8_29") (pintype "passive+no_connect"))
    )
    (net (code "67") (name "unconnected-(U1-PB8-Pad45)") (class "Default")
      (node (ref "U1") (pin "45") (pinfunction "PB8_45") (pintype "passive+no_connect"))
    )
    (net (code "68") (name "unconnected-(U1-PB9-Pad46)") (class "Default")
      (node (ref "U1") (pin "46") (pinfunction "PB9_46") (pintype "passive+no_connect"))
    )
    (net (code "69") (name "unconnected-(U1-PB15-Pad28)") (class "Default")
      (node (ref "U1") (pin "28") (pinfunction "PB15_28") (pintype "passive+no_connect"))
    )
    (net (code "70") (name "unconnected-(U1-PC13-Pad2)") (class "Default")
      (node (ref "U1") (pin "2") (pinfunction "PC13_2") (pintype "passive+no_connect"))
    )
    (net (code "71") (name "unconnected-(U1-PC_15-OSC32_OUT-Pad4)") (class "Default")
      (node (ref "U1") (pin "4") (pinfunction "PC_15-OSC32_OUT_4") (pintype "passive+no_connect"))
    )
    (net (code "72") (name "unconnected-(U6-NC-Pad3)") (class "Default")
      (node (ref "U6") (pin "3") (pinfunction "NC_3") (pintype "passive+no_connect"))
    )
    (net (code "73") (name "unconnected-(U6-NC-Pad5)") (class "Default")
      (node (ref "U6") (pin "5") (pinfunction "NC_5") (pintype "passive+no_connect"))
    )
  )
)
